# Nano_Breakout.net
KiCad netlist of a schematic drawn in EAGLE
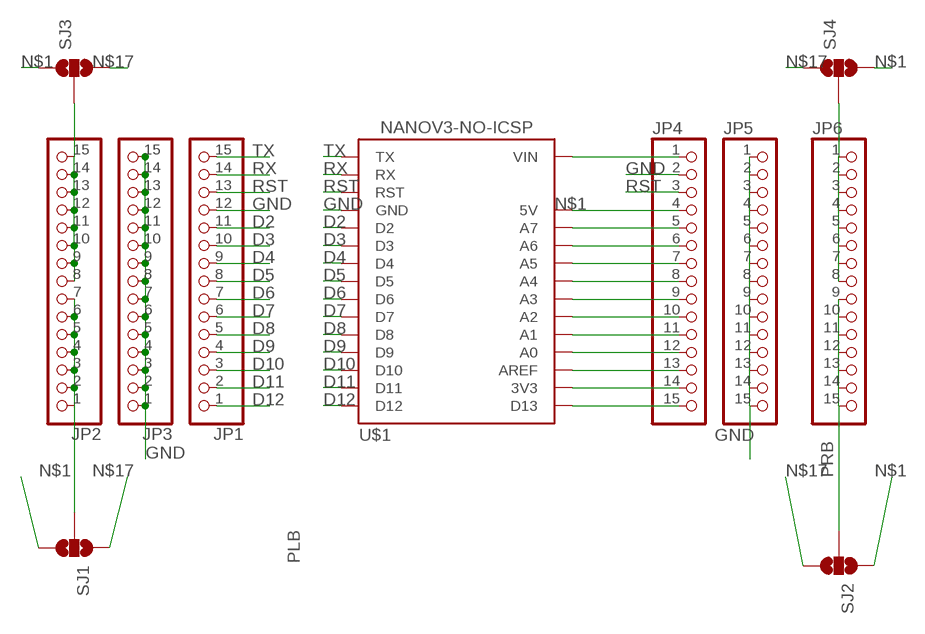
[diagram p0: schematic, sheet 1]

(export (version "E")
  (design (tool "Eeschema 10.0.6"))
  (components
    (comp (ref "JP1")
      (value "PINHD-1X15")
      (footprint "eagle-import:1X15")
      (libsource (lib "eagle-import") (part "PINHD-1X15"))
    )
    (comp (ref "JP2")
      (value "PINHD-1X15")
      (footprint "eagle-import:1X15")
      (libsource (lib "eagle-import") (part "PINHD-1X15"))
    )
    (comp (ref "JP3")
      (value "PINHD-1X15")
      (footprint "eagle-import:1X15")
      (libsource (lib "eagle-import") (part "PINHD-1X15"))
    )
    (comp (ref "JP4")
      (value "PINHD-1X15")
      (footprint "eagle-import:1X15")
      (libsource (lib "eagle-import") (part "PINHD-1X15"))
    )
    (comp (ref "JP5")
      (value "PINHD-1X15")
      (footprint "eagle-import:1X15")
      (libsource (lib "eagle-import") (part "PINHD-1X15"))
    )
    (comp (ref "JP6")
      (value "PINHD-1X15")
      (footprint "eagle-import:1X15")
      (libsource (lib "eagle-import") (part "PINHD-1X15"))
    )
    (comp (ref "SJ1")
      (value "JUMPER-PAD-3-NOFULL_BOX_SILK")
      (footprint "eagle-import:PAD-JUMPER-3-NO_YES_SILK_FULL_BOX")
      (libsource (lib "eagle-import") (part "JUMPER-PAD-3-NOFULL_BOX_SILK"))
    )
    (comp (ref "SJ2")
      (value "JUMPER-PAD-3-NOFULL_BOX_SILK")
      (footprint "eagle-import:PAD-JUMPER-3-NO_YES_SILK_FULL_BOX")
      (libsource (lib "eagle-import") (part "JUMPER-PAD-3-NOFULL_BOX_SILK"))
    )
    (comp (ref "SJ3")
      (value "JUMPER-PAD-3-NOFULL_BOX_SILK")
      (footprint "eagle-import:PAD-JUMPER-3-NO_YES_SILK_FULL_BOX")
      (libsource (lib "eagle-import") (part "JUMPER-PAD-3-NOFULL_BOX_SILK"))
    )
    (comp (ref "SJ4")
      (value "JUMPER-PAD-3-NOFULL_BOX_SILK")
      (footprint "eagle-import:PAD-JUMPER-3-NO_YES_SILK_FULL_BOX")
      (libsource (lib "eagle-import") (part "JUMPER-PAD-3-NOFULL_BOX_SILK"))
    )
    (comp (ref "U$1")
      (value "NANOV3-NO-ICSP")
      (footprint "eagle-import:NANOV3-NO-ICSP")
      (libsource (lib "eagle-import") (part "NANOV3-NO-ICSP"))
    )
  )
  (nets
    (net (code "1") (name "/D2") (class "Default")
      (node (ref "JP1") (pin "11") (pinfunction "11_11") (pintype "passive"))
      (node (ref "U$1") (pin "D2") (pinfunction "D2_D2") (pintype "bidirectional"))
    )
    (net (code "2") (name "/D3") (class "Default")
      (node (ref "JP1") (pin "10") (pinfunction "10_10") (pintype "passive"))
      (node (ref "U$1") (pin "D3") (pinfunction "D3_D3") (pintype "bidirectional"))
    )
    (net (code "3") (name "/D4") (class "Default")
      (node (ref "JP1") (pin "9") (pinfunction "9_9") (pintype "passive"))
      (node (ref "U$1") (pin "D4") (pinfunction "D4_D4") (pintype "bidirectional"))
    )
    (net (code "4") (name "/D5") (class "Default")
      (node (ref "JP1") (pin "8") (pinfunction "8_8") (pintype "passive"))
      (node (ref "U$1") (pin "D5") (pinfunction "D5_D5") (pintype "bidirectional"))
    )
    (net (code "5") (name "/D6") (class "Default")
      (node (ref "JP1") (pin "7") (pinfunction "7_7") (pintype "passive"))
      (node (ref "U$1") (pin "D6") (pinfunction "D6_D6") (pintype "bidirectional"))
    )
    (net (code "6") (name "/D7") (class "Default")
      (node (ref "JP1") (pin "6") (pinfunction "6_6") (pintype "passive"))
      (node (ref "U$1") (pin "D7") (pinfunction "D7_D7") (pintype "bidirectional"))
    )
    (net (code "7") (name "/D8") (class "Default")
      (node (ref "JP1") (pin "5") (pinfunction "5_5") (pintype "passive"))
      (node (ref "U$1") (pin "D8") (pinfunction "D8_D8") (pintype "bidirectional"))
    )
    (net (code "8") (name "/D9") (class "Default")
      (node (ref "JP1") (pin "4") (pinfunction "4_4") (pintype "passive"))
      (node (ref "U$1") (pin "D9") (pinfunction "D9_D9") (pintype "bidirectional"))
    )
    (net (code "9") (name "/D10") (class "Default")
      (node (ref "JP1") (pin "3") (pinfunction "3_3") (pintype "passive"))
      (node (ref "U$1") (pin "D10") (pinfunction "D10_D10") (pintype "bidirectional"))
    )
    (net (code "10") (name "/D11") (class "Default")
      (node (ref "JP1") (pin "2") (pinfunction "2_2") (pintype "passive"))
      (node (ref "U$1") (pin "D11") (pinfunction "D11_D11") (pintype "bidirectional"))
    )
    (net (code "11") (name "/D12") (class "Default")
      (node (ref "JP1") (pin "1") (pinfunction "1_1") (pintype "passive"))
      (node (ref "U$1") (pin "D12") (pinfunction "D12_D12") (pintype "bidirectional"))
    )
    (net (code "12") (name "/GND") (class "Default")
      (node (ref "JP1") (pin "12") (pinfunction "12_12") (pintype "passive"))
      (node (ref "JP3") (pin "1") (pinfunction "1_1") (pintype "passive"))
      (node (ref "JP3") (pin "10") (pinfunction "10_10") (pintype "passive"))
      (node (ref "JP3") (pin "11") (pinfunction "11_11") (pintype "passive"))
      (node (ref "JP3") (pin "12") (pinfunction "12_12") (pintype "passive"))
      (node (ref "JP3") (pin "13") (pinfunction "13_13") (pintype "passive"))
      (node (ref "JP3") (pin "14") (pinfunction "14_14") (pintype "passive"))
      (node (ref "JP3") (pin "15") (pinfunction "15_15") (pintype "passive"))
      (node (ref "JP3") (pin "2") (pinfunction "2_2") (pintype "passive"))
      (node (ref "JP3") (pin "3") (pinfunction "3_3") (pintype "passive"))
      (node (ref "JP3") (pin "4") (pinfunction "4_4") (pintype "passive"))
      (node (ref "JP3") (pin "5") (pinfunction "5_5") (pintype "passive"))
      (node (ref "JP3") (pin "6") (pinfunction "6_6") (pintype "passive"))
      (node (ref "JP3") (pin "7") (pinfunction "7_7") (pintype "passive"))
      (node (ref "JP3") (pin "8") (pinfunction "8_8") (pintype "passive"))
      (node (ref "JP3") (pin "9") (pinfunction "9_9") (pintype "passive"))
      (node (ref "JP4") (pin "2") (pinfunction "2_2") (pintype "passive"))
      (node (ref "JP5") (pin "1") (pinfunction "1_1") (pintype "passive"))
      (node (ref "JP5") (pin "10") (pinfunction "10_10") (pintype "passive"))
      (node (ref "JP5") (pin "11") (pinfunction "11_11") (pintype "passive"))
      (node (ref "JP5") (pin "12") (pinfunction "12_12") (pintype "passive"))
      (node (ref "JP5") (pin "13") (pinfunction "13_13") (pintype "passive"))
      (node (ref "JP5") (pin "14") (pinfunction "14_14") (pintype "passive"))
      (node (ref "JP5") (pin "15") (pinfunction "15_15") (pintype "passive"))
      (node (ref "JP5") (pin "2") (pinfunction "2_2") (pintype "passive"))
      (node (ref "JP5") (pin "3") (pinfunction "3_3") (pintype "passive"))
      (node (ref "JP5") (pin "4") (pinfunction "4_4") (pintype "passive"))
      (node (ref "JP5") (pin "5") (pinfunction "5_5") (pintype "passive"))
      (node (ref "JP5") (pin "6") (pinfunction "6_6") (pintype "passive"))
      (node (ref "JP5") (pin "7") (pinfunction "7_7") (pintype "passive"))
      (node (ref "JP5") (pin "8") (pinfunction "8_8") (pintype "passive"))
      (node (ref "JP5") (pin "9") (pinfunction "9_9") (pintype "passive"))
      (node (ref "U$1") (pin "GND@1") (pinfunction "GND_GND@1") (pintype "power_in"))
      (node (ref "U$1") (pin "GND@2") (pinfunction "GND_GND@2") (pintype "power_in"))
    )
    (net (code "13") (name "/N$1") (class "Default")
      (node (ref "JP4") (pin "4") (pinfunction "4_4") (pintype "passive"))
      (node (ref "SJ1") (pin "3") (pinfunction "3_3") (pintype "passive"))
      (node (ref "SJ2") (pin "1") (pinfunction "1_1") (pintype "passive"))
      (node (ref "SJ3") (pin "1") (pinfunction "1_1") (pintype "passive"))
      (node (ref "SJ4") (pin "3") (pinfunction "3_3") (pintype "passive"))
      (node (ref "U$1") (pin "5V") (pinfunction "5V_5V") (pintype "bidirectional"))
    )
    (net (code "14") (name "/N$17") (class "Default")
      (node (ref "JP4") (pin "14") (pinfunction "14_14") (pintype "passive"))
      (node (ref "SJ1") (pin "1") (pinfunction "1_1") (pintype "passive"))
      (node (ref "SJ2") (pin "3") (pinfunction "3_3") (pintype "passive"))
      (node (ref "SJ3") (pin "3") (pinfunction "3_3") (pintype "passive"))
      (node (ref "SJ4") (pin "1") (pinfunction "1_1") (pintype "passive"))
      (node (ref "U$1") (pin "3V3") (pinfunction "3V3_3V3") (pintype "output"))
    )
    (net (code "15") (name "/PLB") (class "Default")
      (node (ref "JP2") (pin "1") (pinfunction "1_1") (pintype "passive"))
      (node (ref "JP2") (pin "2") (pinfunction "2_2") (pintype "passive"))
      (node (ref "JP2") (pin "3") (pinfunction "3_3") (pintype "passive"))
      (node (ref "JP2") (pin "4") (pinfunction "4_4") (pintype "passive"))
      (node (ref "JP2") (pin "5") (pinfunction "5_5") (pintype "passive"))
      (node (ref "JP2") (pin "6") (pinfunction "6_6") (pintype "passive"))
      (node (ref "JP2") (pin "7") (pinfunction "7_7") (pintype "passive"))
      (node (ref "SJ1") (pin "2") (pinfunction "2_2") (pintype "passive"))
    )
    (net (code "16") (name "/PRB") (class "Default")
      (node (ref "JP6") (pin "10") (pinfunction "10_10") (pintype "passive"))
      (node (ref "JP6") (pin "11") (pinfunction "11_11") (pintype "passive"))
      (node (ref "JP6") (pin "12") (pinfunction "12_12") (pintype "passive"))
      (node (ref "JP6") (pin "13") (pinfunction "13_13") (pintype "passive"))
      (node (ref "JP6") (pin "14") (pinfunction "14_14") (pintype "passive"))
      (node (ref "JP6") (pin "15") (pinfunction "15_15") (pintype "passive"))
      (node (ref "JP6") (pin "9") (pinfunction "9_9") (pintype "passive"))
      (node (ref "SJ2") (pin "2") (pinfunction "2_2") (pintype "passive"))
    )
    (net (code "17") (name "/RST") (class "Default")
      (node (ref "JP1") (pin "13") (pinfunction "13_13") (pintype "passive"))
      (node (ref "JP4") (pin "3") (pinfunction "3_3") (pintype "passive"))
      (node (ref "U$1") (pin "RST1") (pinfunction "RST_RST1") (pintype "input"))
      (node (ref "U$1") (pin "RST2") (pinfunction "RST_RST2") (pintype "input"))
    )
    (net (code "18") (name "/RX") (class "Default")
      (node (ref "JP1") (pin "14") (pinfunction "14_14") (pintype "passive"))
      (node (ref "U$1") (pin "RX") (pinfunction "RX_RX") (pintype "bidirectional"))
    )
    (net (code "19") (name "/TX") (class "Default")
      (node (ref "JP1") (pin "15") (pinfunction "15_15") (pintype "passive"))
      (node (ref "U$1") (pin "TX") (pinfunction "TX_TX") (pintype "bidirectional"))
    )
    (net (code "20") (name "Net-(JP2-Pad10)") (class "Default")
      (node (ref "JP2") (pin "10") (pinfunction "10_10") (pintype "passive"))
      (node (ref "JP2") (pin "11") (pinfunction "11_11") (pintype "passive"))
      (node (ref "JP2") (pin "12") (pinfunction "12_12") (pintype "passive"))
      (node (ref "JP2") (pin "13") (pinfunction "13_13") (pintype "passive"))
      (node (ref "JP2") (pin "14") (pinfunction "14_14") (pintype "passive"))
      (node (ref "JP2") (pin "15") (pinfunction "15_15") (pintype "passive"))
      (node (ref "JP2") (pin "8") (pinfunction "8_8") (pintype "passive"))
      (node (ref "JP2") (pin "9") (pinfunction "9_9") (pintype "passive"))
      (node (ref "SJ3") (pin "2") (pinfunction "2_2") (pintype "passive"))
    )
    (net (code "21") (name "Net-(JP4-Pad1)") (class "Default")
      (node (ref "JP4") (pin "1") (pinfunction "1_1") (pintype "passive"))
      (node (ref "U$1") (pin "VIN") (pinfunction "VIN_VIN") (pintype "power_in"))
    )
    (net (code "22") (name "Net-(JP4-Pad5)") (class "Default")
      (node (ref "JP4") (pin "5") (pinfunction "5_5") (pintype "passive"))
      (node (ref "U$1") (pin "A7") (pinfunction "A7_A7") (pintype "input"))
    )
    (net (code "23") (name "Net-(JP4-Pad6)") (class "Default")
      (node (ref "JP4") (pin "6") (pinfunction "6_6") (pintype "passive"))
      (node (ref "U$1") (pin "A6") (pinfunction "A6_A6") (pintype "input"))
    )
    (net (code "24") (name "Net-(JP4-Pad7)") (class "Default")
      (node (ref "JP4") (pin "7") (pinfunction "7_7") (pintype "passive"))
      (node (ref "U$1") (pin "A5") (pinfunction "A5_A5") (pintype "input"))
    )
    (net (code "25") (name "Net-(JP4-Pad8)") (class "Default")
      (node (ref "JP4") (pin "8") (pinfunction "8_8") (pintype "passive"))
      (node (ref "U$1") (pin "A4") (pinfunction "A4_A4") (pintype "input"))
    )
    (net (code "26") (name "Net-(JP4-Pad9)") (class "Default")
      (node (ref "JP4") (pin "9") (pinfunction "9_9") (pintype "passive"))
      (node (ref "U$1") (pin "A3") (pinfunction "A3_A3") (pintype "input"))
    )
    (net (code "27") (name "Net-(JP4-Pad10)") (class "Default")
      (node (ref "JP4") (pin "10") (pinfunction "10_10") (pintype "passive"))
      (node (ref "U$1") (pin "A2") (pinfunction "A2_A2") (pintype "input"))
    )
    (net (code "28") (name "Net-(JP4-Pad11)") (class "Default")
      (node (ref "JP4") (pin "11") (pinfunction "11_11") (pintype "passive"))
      (node (ref "U$1") (pin "A1") (pinfunction "A1_A1") (pintype "input"))
    )
    (net (code "29") (name "Net-(JP4-Pad12)") (class "Default")
      (node (ref "JP4") (pin "12") (pinfunction "12_12") (pintype "passive"))
      (node (ref "U$1") (pin "A0") (pinfunction "A0_A0") (pintype "input"))
    )
    (net (code "30") (name "Net-(JP4-Pad13)") (class "Default")
      (node (ref "JP4") (pin "13") (pinfunction "13_13") (pintype "passive"))
      (node (ref "U$1") (pin "AREF") (pinfunction "AREF_AREF") (pintype "input"))
    )
    (net (code "31") (name "Net-(JP4-Pad15)") (class "Default")
      (node (ref "JP4") (pin "15") (pinfunction "15_15") (pintype "passive"))
      (node (ref "U$1") (pin "D13") (pinfunction "D13_D13") (pintype "bidirectional"))
    )
    (net (code "32") (name "Net-(JP6-Pad1)") (class "Default")
      (node (ref "JP6") (pin "1") (pinfunction "1_1") (pintype "passive"))
      (node (ref "JP6") (pin "2") (pinfunction "2_2") (pintype "passive"))
      (node (ref "JP6") (pin "3") (pinfunction "3_3") (pintype "passive"))
      (node (ref "JP6") (pin "4") (pinfunction "4_4") (pintype "passive"))
      (node (ref "JP6") (pin "5") (pinfunction "5_5") (pintype "passive"))
      (node (ref "JP6") (pin "6") (pinfunction "6_6") (pintype "passive"))
      (node (ref "JP6") (pin "7") (pinfunction "7_7") (pintype "passive"))
      (node (ref "JP6") (pin "8") (pinfunction "8_8") (pintype "passive"))
      (node (ref "SJ4") (pin "2") (pinfunction "2_2") (pintype "passive"))
    )
  )
)
